# Top.net
KiCad netlist of a schematic drawn in Altium Designer
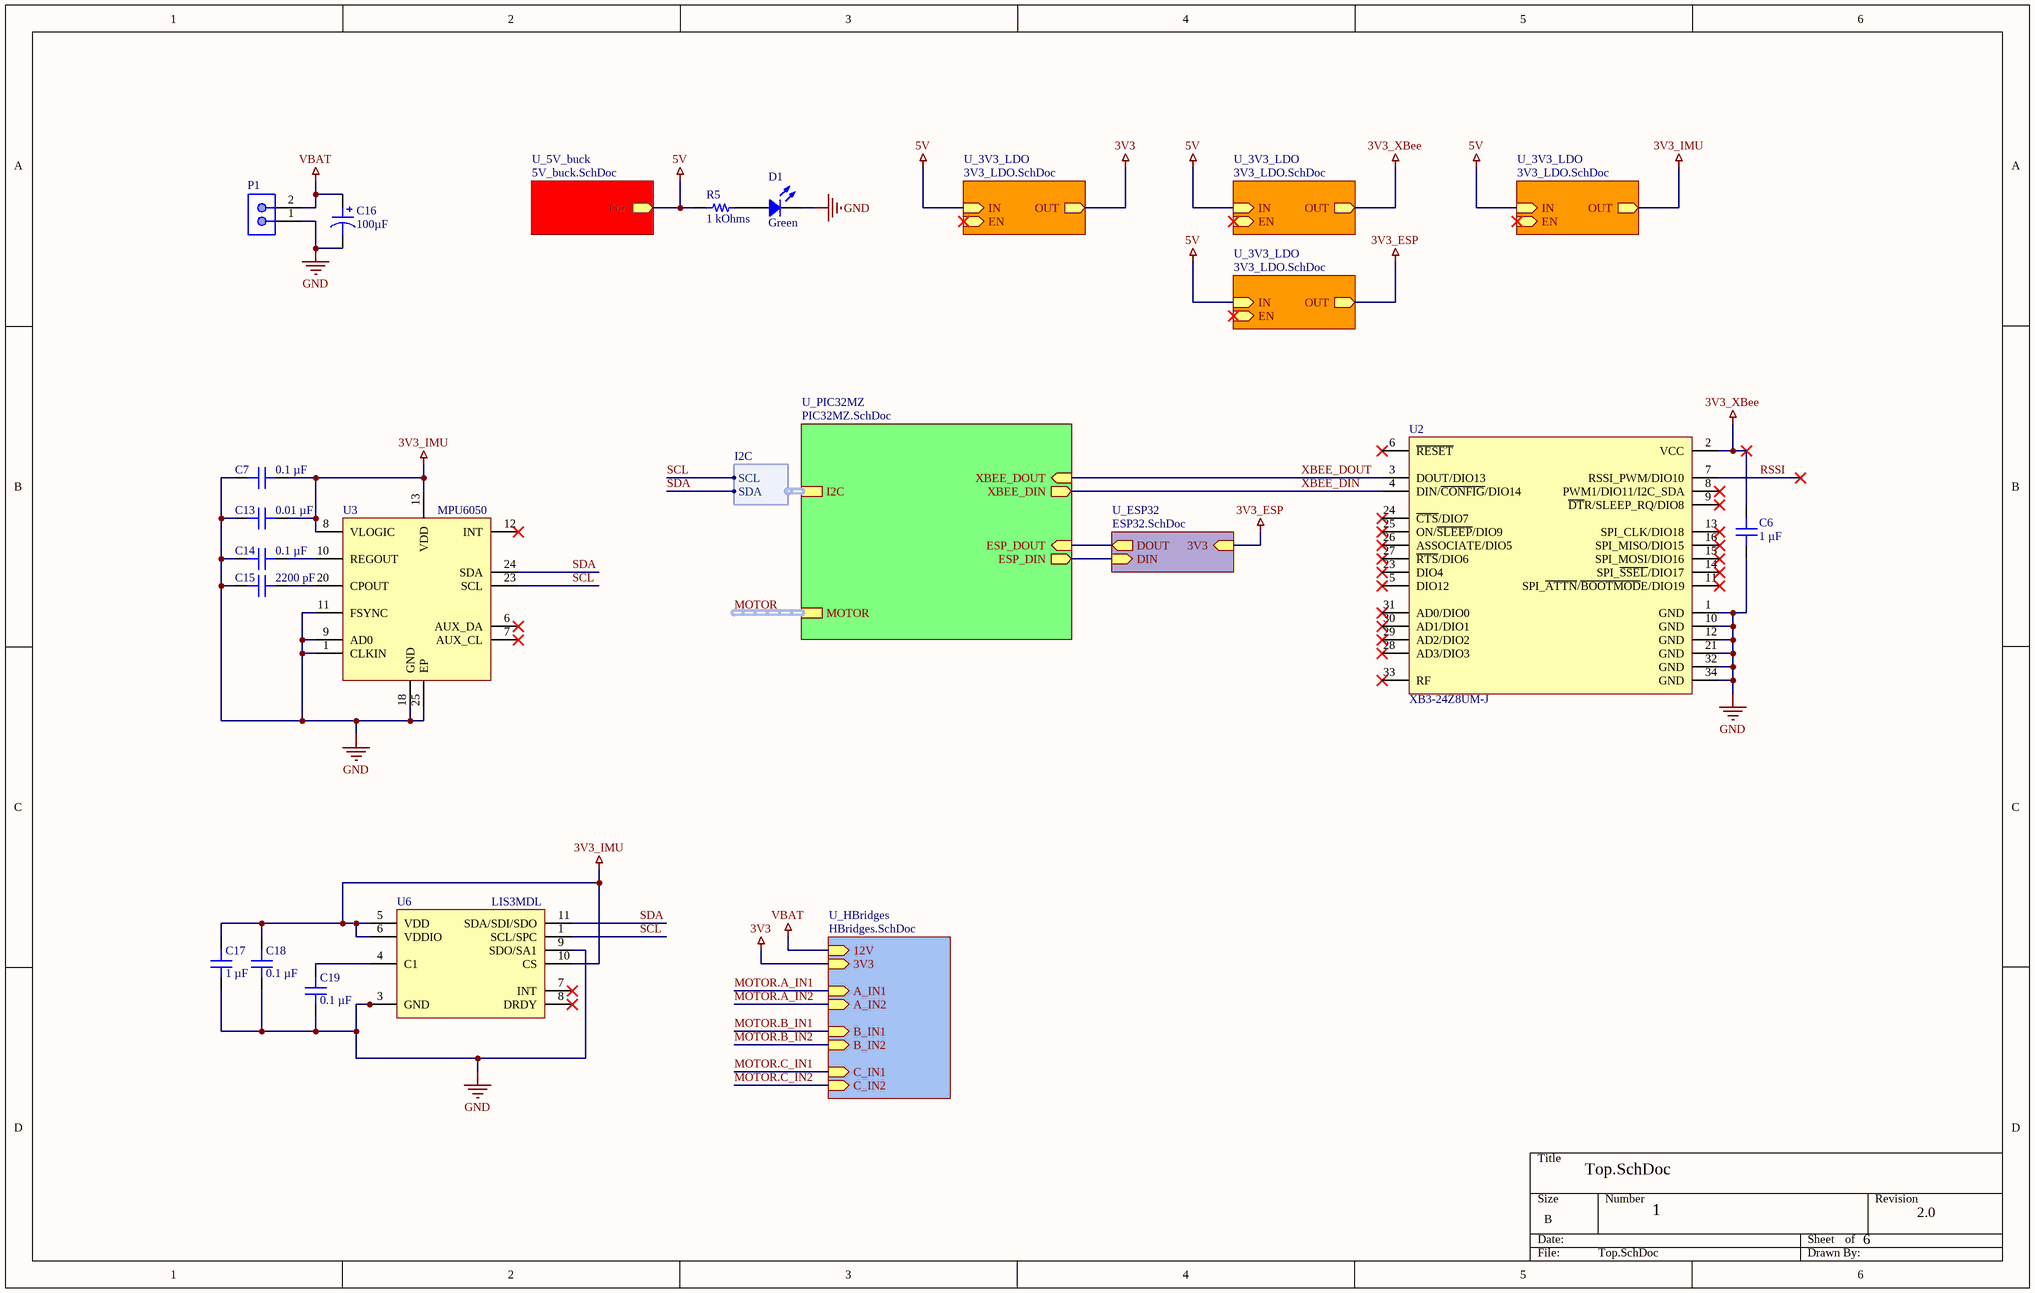
[diagram p0: Top.SchDoc]

(export (version "E")
  (design (tool "Eeschema 10.0.6"))
  (components
    (comp (ref "C6")
      (value "1 µF")
      (footprint "CAP 0402_1005")
      (description "CAP CER 0.1UF 16V X7R 0402")
      (fields (field (name "PART NUMBER") "C0402C104K4RACAUTO") (field (name "MANUFACTURER") "KEMET"))
      (libsource (lib "Celestial Altium Library - altium_library") (part "Capacitor"))
    )
    (comp (ref "C7")
      (value "0.1 µF")
      (footprint "CAP 0402_1005")
      (description "CAP CER 0.1UF 16V X7R 0402")
      (fields (field (name "PART NUMBER") "C0402C104K4RACAUTO") (field (name "MANUFACTURER") "KEMET"))
      (libsource (lib "Celestial Altium Library - altium_library") (part "Capacitor"))
    )
    (comp (ref "C13")
      (value "0.01 µF")
      (footprint "CAP 0402_1005")
      (description "CAP CER 0.1UF 16V X7R 0402")
      (fields (field (name "PART NUMBER") "C0402C104K4RACAUTO") (field (name "MANUFACTURER") "KEMET"))
      (libsource (lib "Celestial Altium Library - altium_library") (part "Capacitor"))
    )
    (comp (ref "C14")
      (value "0.1 µF")
      (footprint "CAP 0402_1005")
      (description "CAP CER 0.1UF 16V X7R 0402")
      (fields (field (name "PART NUMBER") "C0402C104K4RACAUTO") (field (name "MANUFACTURER") "KEMET"))
      (libsource (lib "Celestial Altium Library - altium_library") (part "Capacitor"))
    )
    (comp (ref "C15")
      (value "2200 pF")
      (footprint "CAP 0402_1005")
      (description "CAP CER 0.1UF 16V X7R 0402")
      (fields (field (name "PART NUMBER") "C0402C104K4RACAUTO") (field (name "MANUFACTURER") "KEMET"))
      (libsource (lib "Celestial Altium Library - altium_library") (part "Capacitor"))
    )
    (comp (ref "C16")
      (value "100µF")
      (footprint "CAP POL 2917_7343")
      (description "CAP TANT 100UF 20% 20V 2917")
      (fields (field (name "PART NUMBER") "293D107X0020E2TE3") (field (name "MANUFACTURER") "Vishay Sprague"))
      (libsource (lib "Celestial Altium Library - altium_library") (part "Polarised Capacitor"))
    )
    (comp (ref "C17")
      (value "1 µF")
      (footprint "CAP 0402_1005")
      (description "CAP CER 0.1UF 16V X7R 0402")
      (fields (field (name "PART NUMBER") "C0402C104K4RACAUTO") (field (name "MANUFACTURER") "KEMET"))
      (libsource (lib "Celestial Altium Library - altium_library") (part "Capacitor"))
    )
    (comp (ref "C18")
      (value "0.1 µF")
      (footprint "CAP 0402_1005")
      (description "CAP CER 0.1UF 16V X7R 0402")
      (fields (field (name "PART NUMBER") "C0402C104K4RACAUTO") (field (name "MANUFACTURER") "KEMET"))
      (libsource (lib "Celestial Altium Library - altium_library") (part "Capacitor"))
    )
    (comp (ref "C19")
      (value "0.1 µF")
      (footprint "CAP 0402_1005")
      (description "CAP CER 0.1UF 16V X7R 0402")
      (fields (field (name "PART NUMBER") "C0402C104K4RACAUTO") (field (name "MANUFACTURER") "KEMET"))
      (libsource (lib "Celestial Altium Library - altium_library") (part "Capacitor"))
    )
    (comp (ref "D1")
      (value "Green")
      (footprint "LED 0603_1608 GREEN")
      (description "1.6X0.8MM LC GREEN PIXSOLED DOME")
      (fields (field (name "PART NUMBER") "XZCDGK53W-8VF") (field (name "MANUFACTURER") "SunLED"))
      (libsource (lib "Celestial Altium Library - altium_library") (part "LED"))
    )
    (comp (ref "P1")
      (value "2 pin 2mm JST Male")
      (footprint "2pin - 2mm JST male")
      (libsource (lib "IC") (part "2 pin 2mm JST Male"))
    )
    (comp (ref "R5")
      (value "1 kOhms")
      (footprint "YAGEO RES 0402_1005")
      (description "RES 1K OHM 1% 1/16W 0402")
      (fields (field (name "PART NUMBER") "RC0402FR-071KL") (field (name "MANUFACTURER") "Yageo"))
      (libsource (lib "Celestial Altium Library - altium_library") (part "Resistor"))
    )
    (comp (ref "U2")
      (value "XB3-24Z8UM-J")
      (footprint "IC:XCVR_XB3-24Z8UM-J")
      (description "802.15.4 Zigbee Transceiver Module 2.4GHz Antenna Not Included, U.FL Surface Mount")
      (fields (field (name "MF") "Digi International"))
      (libsource (lib "IC") (part "XB3-24Z8UM-J"))
    )
    (comp (ref "U3") (value "MPU6050") (footprint "IC_MPU6050") (libsource (lib "IC") (part "MPU6050")))
    (comp (ref "U6")
      (value "LIS3MDL")
      (footprint "LGA12_ST")
      (description "Magnetometer")
      (libsource (lib "IC") (part "LIS3MDL"))
    )
  )
  (nets
    (net (code "15") (name "/RSSI") (class "Default")
      (node (ref "U2") (pin "7") (pinfunction "RSSI_PWM/DIO10_7") (pintype "passive+no_connect"))
    )
    (net (code "16") (name "/SCL") (class "Default")
      (node (ref "U3") (pin "23") (pinfunction "SCL_23") (pintype "passive"))
      (node (ref "U6") (pin "1") (pinfunction "SCL/SPC_1") (pintype "passive"))
    )
    (net (code "17") (name "/SDA") (class "Default")
      (node (ref "U3") (pin "24") (pinfunction "SDA_24") (pintype "passive"))
      (node (ref "U6") (pin "11") (pinfunction "SDA/SDI/SDO_11") (pintype "passive"))
    )
    (net (code "18") (name "/XBEE_DIN") (class "Default")
      (node (ref "U2") (pin "4") (pinfunction "DIN/~{CONFIG}/DIO14_4") (pintype "passive"))
    )
    (net (code "19") (name "/XBEE_DOUT") (class "Default")
      (node (ref "U2") (pin "3") (pinfunction "DOUT/DIO13_3") (pintype "passive"))
    )
    (net (code "24") (name "3V3_IMU") (class "Default")
      (node (ref "C13") (pin "1") (pinfunction "1_1") (pintype "passive"))
      (node (ref "C17") (pin "1") (pinfunction "1_1") (pintype "passive"))
      (node (ref "C18") (pin "1") (pinfunction "1_1") (pintype "passive"))
      (node (ref "C7") (pin "1") (pinfunction "1_1") (pintype "passive"))
      (node (ref "U3") (pin "13") (pinfunction "VDD_13") (pintype "passive"))
      (node (ref "U3") (pin "8") (pinfunction "VLOGIC_8") (pintype "passive"))
      (node (ref "U6") (pin "10") (pinfunction "CS_10") (pintype "passive"))
      (node (ref "U6") (pin "5") (pinfunction "VDD_5") (pintype "passive"))
      (node (ref "U6") (pin "6") (pinfunction "VDDIO_6") (pintype "passive"))
    )
    (net (code "25") (name "3V3_XBee") (class "Default")
      (node (ref "C6") (pin "1") (pinfunction "1_1") (pintype "passive"))
      (node (ref "U2") (pin "2") (pinfunction "VCC_2") (pintype "power_in"))
    )
    (net (code "26") (name "5V") (class "Default")
      (node (ref "R5") (pin "1") (pinfunction "1_1") (pintype "passive"))
    )
    (net (code "27") (name "GND") (class "Default")
      (node (ref "C13") (pin "2") (pinfunction "2_2") (pintype "passive"))
      (node (ref "C14") (pin "2") (pinfunction "2_2") (pintype "passive"))
      (node (ref "C15") (pin "2") (pinfunction "2_2") (pintype "passive"))
      (node (ref "C16") (pin "2") (pinfunction "2_2") (pintype "passive"))
      (node (ref "C17") (pin "2") (pinfunction "2_2") (pintype "passive"))
      (node (ref "C18") (pin "2") (pinfunction "2_2") (pintype "passive"))
      (node (ref "C19") (pin "2") (pinfunction "2_2") (pintype "passive"))
      (node (ref "C6") (pin "2") (pinfunction "2_2") (pintype "passive"))
      (node (ref "C7") (pin "2") (pinfunction "2_2") (pintype "passive"))
      (node (ref "D1") (pin "2") (pinfunction "2_2") (pintype "passive"))
      (node (ref "P1") (pin "1") (pinfunction "1_1") (pintype "passive"))
      (node (ref "U2") (pin "1") (pinfunction "GND_1") (pintype "power_in"))
      (node (ref "U2") (pin "10") (pinfunction "GND_10") (pintype "power_in"))
      (node (ref "U2") (pin "12") (pinfunction "GND_12") (pintype "power_in"))
      (node (ref "U2") (pin "21") (pinfunction "GND_21") (pintype "power_in"))
      (node (ref "U2") (pin "32") (pinfunction "GND_32") (pintype "power_in"))
      (node (ref "U2") (pin "34") (pinfunction "GND_34") (pintype "power_in"))
      (node (ref "U3") (pin "1") (pinfunction "CLKIN_1") (pintype "passive"))
      (node (ref "U3") (pin "11") (pinfunction "FSYNC_11") (pintype "passive"))
      (node (ref "U3") (pin "18") (pinfunction "GND_18") (pintype "passive"))
      (node (ref "U3") (pin "25") (pinfunction "EP_25") (pintype "passive"))
      (node (ref "U3") (pin "9") (pinfunction "AD0_9") (pintype "passive"))
      (node (ref "U6") (pin "12") (pinfunction "Reserved_12") (pintype "passive"))
      (node (ref "U6") (pin "2") (pinfunction "Reserved_2") (pintype "passive"))
      (node (ref "U6") (pin "3") (pinfunction "GND_3") (pintype "passive"))
      (node (ref "U6") (pin "9") (pinfunction "SDO/SA1_9") (pintype "passive"))
    )
    (net (code "28") (name "Net-(D1-Pad1)") (class "Default")
      (node (ref "D1") (pin "1") (pinfunction "1_1") (pintype "passive"))
      (node (ref "R5") (pin "2") (pinfunction "2_2") (pintype "passive"))
    )
    (net (code "29") (name "Net-(U3-CPOUT)") (class "Default")
      (node (ref "C15") (pin "1") (pinfunction "1_1") (pintype "passive"))
      (node (ref "U3") (pin "20") (pinfunction "CPOUT_20") (pintype "passive"))
    )
    (net (code "30") (name "Net-(U3-REGOUT)") (class "Default")
      (node (ref "C14") (pin "1") (pinfunction "1_1") (pintype "passive"))
      (node (ref "U3") (pin "10") (pinfunction "REGOUT_10") (pintype "passive"))
    )
    (net (code "31") (name "Net-(U6-C1)") (class "Default")
      (node (ref "C19") (pin "1") (pinfunction "1_1") (pintype "passive"))
      (node (ref "U6") (pin "4") (pinfunction "C1_4") (pintype "passive"))
    )
    (net (code "32") (name "VBAT") (class "Default")
      (node (ref "C16") (pin "1") (pinfunction "1_1") (pintype "passive"))
      (node (ref "P1") (pin "2") (pinfunction "2_2") (pintype "passive"))
    )
    (net (code "33") (name "unconnected-(U2-AD0{slash}DIO0-Pad31)") (class "Default")
      (node (ref "U2") (pin "31") (pinfunction "AD0/DIO0_31") (pintype "passive+no_connect"))
    )
    (net (code "34") (name "unconnected-(U2-AD1{slash}DIO1-Pad30)") (class "Default")
      (node (ref "U2") (pin "30") (pinfunction "AD1/DIO1_30") (pintype "passive+no_connect"))
    )
    (net (code "35") (name "unconnected-(U2-AD2{slash}DIO2-Pad29)") (class "Default")
      (node (ref "U2") (pin "29") (pinfunction "AD2/DIO2_29") (pintype "passive+no_connect"))
    )
    (net (code "36") (name "unconnected-(U2-AD3{slash}DIO3-Pad28)") (class "Default")
      (node (ref "U2") (pin "28") (pinfunction "AD3/DIO3_28") (pintype "passive+no_connect"))
    )
    (net (code "37") (name "unconnected-(U2-ASSOCIATE{slash}DIO5-Pad26)") (class "Default")
      (node (ref "U2") (pin "26") (pinfunction "ASSOCIATE/DIO5_26") (pintype "passive+no_connect"))
    )
    (net (code "38") (name "unconnected-(U2-DIO4-Pad23)") (class "Default")
      (node (ref "U2") (pin "23") (pinfunction "DIO4_23") (pintype "passive+no_connect"))
    )
    (net (code "39") (name "unconnected-(U2-DIO12-Pad5)") (class "Default")
      (node (ref "U2") (pin "5") (pinfunction "DIO12_5") (pintype "passive+no_connect"))
    )
    (net (code "40") (name "unconnected-(U2-ON{slash}~{SLEEP}{slash}DIO9-Pad25)") (class "Default")
      (node (ref "U2") (pin "25") (pinfunction "ON/~{SLEEP}/DIO9_25") (pintype "passive+no_connect"))
    )
    (net (code "41") (name "unconnected-(U2-PWM1{slash}DIO11{slash}I2C_SDA-Pad8)") (class "Default")
      (node (ref "U2") (pin "8") (pinfunction "PWM1/DIO11/I2C_SDA_8") (pintype "passive+no_connect"))
    )
    (net (code "42") (name "unconnected-(U2-RF-Pad33)") (class "Default")
      (node (ref "U2") (pin "33") (pinfunction "RF_33") (pintype "passive+no_connect"))
    )
    (net (code "43") (name "unconnected-(U2-SPI_CLK{slash}DIO18-Pad13)") (class "Default")
      (node (ref "U2") (pin "13") (pinfunction "SPI_CLK/DIO18_13") (pintype "passive+no_connect"))
    )
    (net (code "44") (name "unconnected-(U2-SPI_MISO{slash}DIO15-Pad16)") (class "Default")
      (node (ref "U2") (pin "16") (pinfunction "SPI_MISO/DIO15_16") (pintype "passive+no_connect"))
    )
    (net (code "45") (name "unconnected-(U2-SPI_MOSI{slash}DIO16-Pad15)") (class "Default")
      (node (ref "U2") (pin "15") (pinfunction "SPI_MOSI/DIO16_15") (pintype "passive+no_connect"))
    )
    (net (code "46") (name "unconnected-(U2-SPI_~{ATTN}{slash}~{BOOTMOD}E{slash}DIO19-Pad11)") (class "Default")
      (node (ref "U2") (pin "11") (pinfunction "SPI_~{ATTN}/~{BOOTMOD}E/DIO19_11") (pintype "passive+no_connect"))
    )
    (net (code "47") (name "unconnected-(U2-SPI_~{SSEL}{slash}DIO17-Pad14)") (class "Default")
      (node (ref "U2") (pin "14") (pinfunction "SPI_~{SSEL}/DIO17_14") (pintype "passive+no_connect"))
    )
    (net (code "48") (name "unconnected-(U2-~{CTS}{slash}DIO7-Pad24)") (class "Default")
      (node (ref "U2") (pin "24") (pinfunction "~{CTS}/DIO7_24") (pintype "passive+no_connect"))
    )
    (net (code "49") (name "unconnected-(U2-~{DT}R{slash}SLEEP_RQ{slash}DIO8-Pad9)") (class "Default")
      (node (ref "U2") (pin "9") (pinfunction "~{DT}R/SLEEP_RQ/DIO8_9") (pintype "passive+no_connect"))
    )
    (net (code "50") (name "unconnected-(U2-~{RESET}-Pad6)") (class "Default")
      (node (ref "U2") (pin "6") (pinfunction "~{RESET}_6") (pintype "passive+no_connect"))
    )
    (net (code "51") (name "unconnected-(U2-~{RTS}{slash}DIO6-Pad27)") (class "Default")
      (node (ref "U2") (pin "27") (pinfunction "~{RTS}/DIO6_27") (pintype "passive+no_connect"))
    )
    (net (code "52") (name "unconnected-(U3-AUX_CL-Pad7)") (class "Default")
      (node (ref "U3") (pin "7") (pinfunction "AUX_CL_7") (pintype "passive+no_connect"))
    )
    (net (code "53") (name "unconnected-(U3-AUX_DA-Pad6)") (class "Default")
      (node (ref "U3") (pin "6") (pinfunction "AUX_DA_6") (pintype "passive+no_connect"))
    )
    (net (code "54") (name "unconnected-(U3-INT-Pad12)") (class "Default")
      (node (ref "U3") (pin "12") (pinfunction "INT_12") (pintype "passive+no_connect"))
    )
    (net (code "55") (name "unconnected-(U6-DRDY-Pad8)") (class "Default")
      (node (ref "U6") (pin "8") (pinfunction "DRDY_8") (pintype "passive+no_connect"))
    )
    (net (code "56") (name "unconnected-(U6-INT-Pad7)") (class "Default")
      (node (ref "U6") (pin "7") (pinfunction "INT_7") (pintype "passive+no_connect"))
    )
  )
)
